# Hydra_OSP.net
KiCad netlist of a schematic drawn in EAGLE
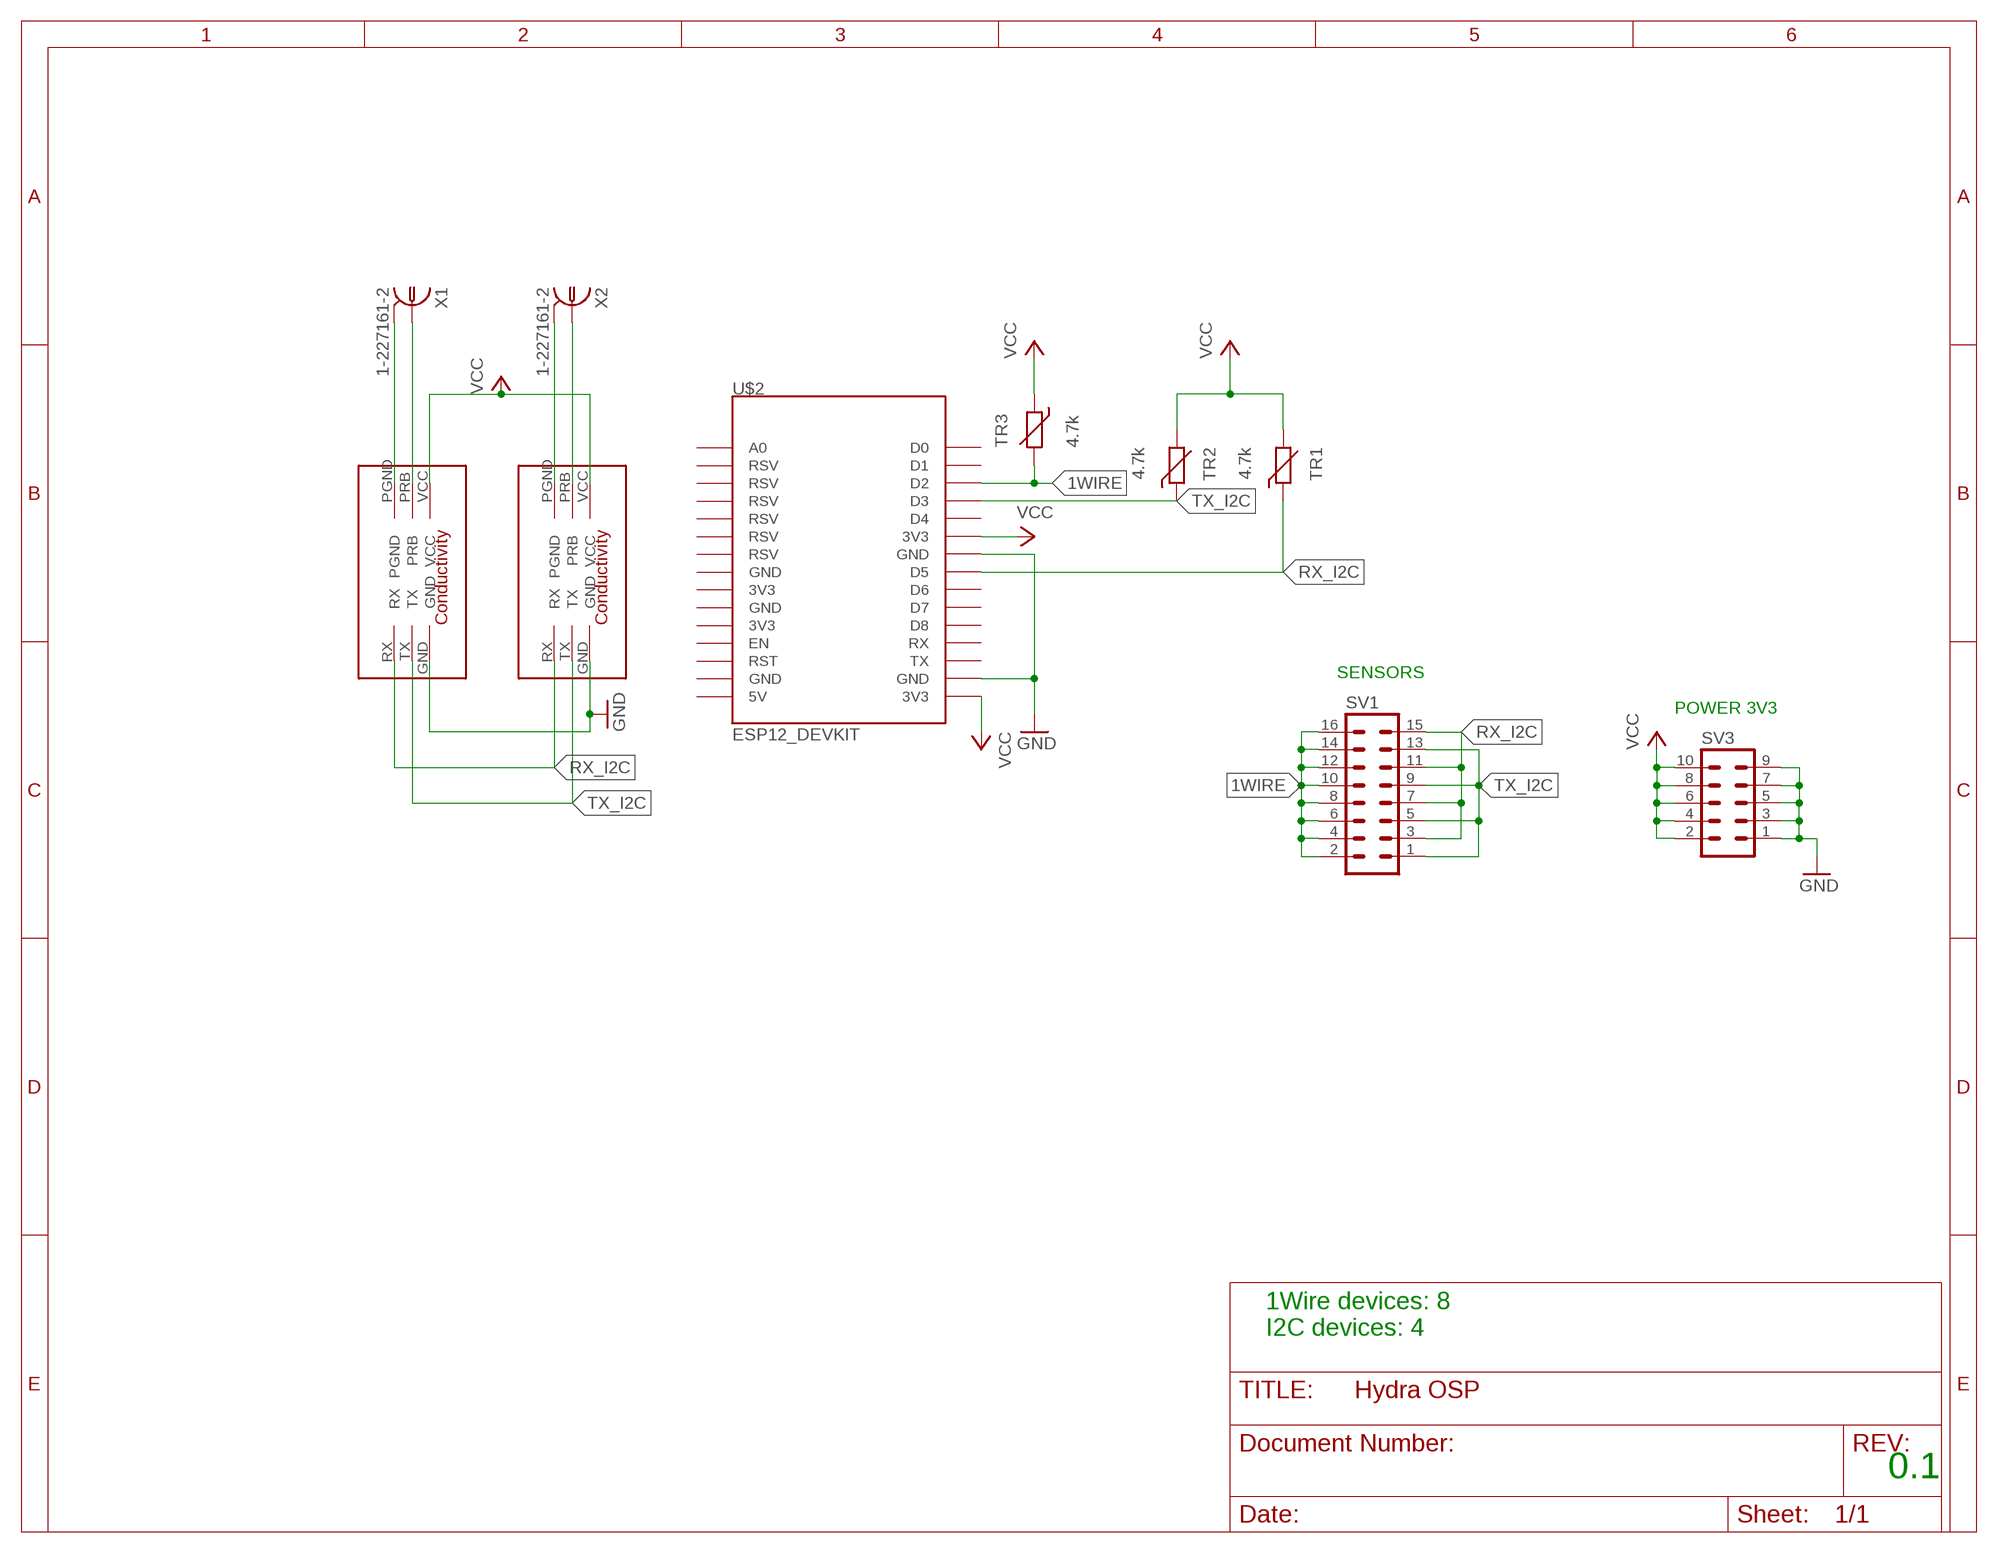
[diagram p0: schematic, sheet 1]

(export (version "E")
  (design (tool "Eeschema 10.0.6"))
  (components
    (comp (ref "SV1")
      (value "MA08-2")
      (footprint "eagle-import:MA08-2")
      (libsource (lib "eagle-import") (part "MA08-2"))
    )
    (comp (ref "SV3")
      (value "MA05-2")
      (footprint "eagle-import:MA05-2")
      (libsource (lib "eagle-import") (part "MA05-2"))
    )
    (comp (ref "TR1")
      (value "4.7k")
      (footprint "eagle-import:R-5")
      (libsource (lib "eagle-import") (part "THERMISTOR_R-5"))
    )
    (comp (ref "TR2")
      (value "4.7k")
      (footprint "eagle-import:R-5")
      (libsource (lib "eagle-import") (part "THERMISTOR_R-5"))
    )
    (comp (ref "TR3")
      (value "4.7k")
      (footprint "eagle-import:R-5")
      (libsource (lib "eagle-import") (part "THERMISTOR_R-5"))
    )
    (comp (ref "U$1")
      (value "ATLSCI_COND")
      (footprint "eagle-import:ATLAS_SCI_COND")
      (libsource (lib "eagle-import") (part "ATLSCI_COND"))
    )
    (comp (ref "U$2")
      (value "ESP12_DEVKIT")
      (footprint "eagle-import:ESP12_DEVKIT")
      (libsource (lib "eagle-import") (part "ESP12_DEVKIT"))
    )
    (comp (ref "U$3")
      (value "ATLSCI_COND")
      (footprint "eagle-import:ATLAS_SCI_COND")
      (libsource (lib "eagle-import") (part "ATLSCI_COND"))
    )
    (comp (ref "X1")
      (value "1-227161-2")
      (footprint "eagle-import:AMP_227161")
      (libsource (lib "eagle-import") (part "?2271611--2"))
    )
    (comp (ref "X2")
      (value "1-227161-2")
      (footprint "eagle-import:AMP_227161")
      (libsource (lib "eagle-import") (part "?2271611--2"))
    )
  )
  (nets
    (net (code "1") (name "1WIRE") (class "Default")
      (node (ref "SV1") (pin "10") (pinfunction "10_10") (pintype "passive"))
      (node (ref "SV1") (pin "12") (pinfunction "12_12") (pintype "passive"))
      (node (ref "SV1") (pin "14") (pinfunction "14_14") (pintype "passive"))
      (node (ref "SV1") (pin "16") (pinfunction "16_16") (pintype "passive"))
      (node (ref "SV1") (pin "2") (pinfunction "2_2") (pintype "passive"))
      (node (ref "SV1") (pin "4") (pinfunction "4_4") (pintype "passive"))
      (node (ref "SV1") (pin "6") (pinfunction "6_6") (pintype "passive"))
      (node (ref "SV1") (pin "8") (pinfunction "8_8") (pintype "passive"))
      (node (ref "TR3") (pin "2") (pinfunction "2_2") (pintype "passive"))
      (node (ref "U$2") (pin "D2") (pinfunction "D2_D2") (pintype "bidirectional"))
    )
    (net (code "2") (name "GND") (class "Default")
      (node (ref "SV3") (pin "1") (pinfunction "1_1") (pintype "passive"))
      (node (ref "SV3") (pin "3") (pinfunction "3_3") (pintype "passive"))
      (node (ref "SV3") (pin "5") (pinfunction "5_5") (pintype "passive"))
      (node (ref "SV3") (pin "7") (pinfunction "7_7") (pintype "passive"))
      (node (ref "SV3") (pin "9") (pinfunction "9_9") (pintype "passive"))
      (node (ref "U$1") (pin "GND") (pinfunction "GND_GND") (pintype "bidirectional"))
      (node (ref "U$2") (pin "GND@2") (pinfunction "GND_GND@2") (pintype "bidirectional"))
      (node (ref "U$2") (pin "GND@3") (pinfunction "GND_GND@3") (pintype "bidirectional"))
      (node (ref "U$3") (pin "GND") (pinfunction "GND_GND") (pintype "bidirectional"))
    )
    (net (code "3") (name "Net-(U$1-PadPGND)") (class "Default")
      (node (ref "U$1") (pin "PGND") (pinfunction "PGND_PGND") (pintype "bidirectional"))
      (node (ref "X1") (pin "2") (pinfunction "2_2") (pintype "passive"))
    )
    (net (code "4") (name "Net-(U$1-PadPRB)") (class "Default")
      (node (ref "U$1") (pin "PRB") (pinfunction "PRB_PRB") (pintype "bidirectional"))
      (node (ref "X1") (pin "1") (pinfunction "1_1") (pintype "passive"))
    )
    (net (code "5") (name "Net-(U$3-PadPGND)") (class "Default")
      (node (ref "U$3") (pin "PGND") (pinfunction "PGND_PGND") (pintype "bidirectional"))
      (node (ref "X2") (pin "2") (pinfunction "2_2") (pintype "passive"))
    )
    (net (code "6") (name "Net-(U$3-PadPRB)") (class "Default")
      (node (ref "U$3") (pin "PRB") (pinfunction "PRB_PRB") (pintype "bidirectional"))
      (node (ref "X2") (pin "1") (pinfunction "1_1") (pintype "passive"))
    )
    (net (code "7") (name "RX_I2C") (class "Default")
      (node (ref "SV1") (pin "11") (pinfunction "11_11") (pintype "passive"))
      (node (ref "SV1") (pin "15") (pinfunction "15_15") (pintype "passive"))
      (node (ref "SV1") (pin "3") (pinfunction "3_3") (pintype "passive"))
      (node (ref "SV1") (pin "7") (pinfunction "7_7") (pintype "passive"))
      (node (ref "TR1") (pin "1") (pinfunction "1_1") (pintype "passive"))
      (node (ref "U$1") (pin "RX") (pinfunction "RX_RX") (pintype "bidirectional"))
      (node (ref "U$2") (pin "D5") (pinfunction "D5_D5") (pintype "bidirectional"))
      (node (ref "U$3") (pin "RX") (pinfunction "RX_RX") (pintype "bidirectional"))
    )
    (net (code "8") (name "TX_I2C") (class "Default")
      (node (ref "SV1") (pin "1") (pinfunction "1_1") (pintype "passive"))
      (node (ref "SV1") (pin "13") (pinfunction "13_13") (pintype "passive"))
      (node (ref "SV1") (pin "5") (pinfunction "5_5") (pintype "passive"))
      (node (ref "SV1") (pin "9") (pinfunction "9_9") (pintype "passive"))
      (node (ref "TR2") (pin "1") (pinfunction "1_1") (pintype "passive"))
      (node (ref "U$1") (pin "TX") (pinfunction "TX_TX") (pintype "bidirectional"))
      (node (ref "U$2") (pin "D3") (pinfunction "D3_D3") (pintype "bidirectional"))
      (node (ref "U$3") (pin "TX") (pinfunction "TX_TX") (pintype "bidirectional"))
    )
    (net (code "9") (name "VCC") (class "Default")
      (node (ref "SV3") (pin "10") (pinfunction "10_10") (pintype "passive"))
      (node (ref "SV3") (pin "2") (pinfunction "2_2") (pintype "passive"))
      (node (ref "SV3") (pin "4") (pinfunction "4_4") (pintype "passive"))
      (node (ref "SV3") (pin "6") (pinfunction "6_6") (pintype "passive"))
      (node (ref "SV3") (pin "8") (pinfunction "8_8") (pintype "passive"))
      (node (ref "TR1") (pin "2") (pinfunction "2_2") (pintype "passive"))
      (node (ref "TR2") (pin "2") (pinfunction "2_2") (pintype "passive"))
      (node (ref "TR3") (pin "1") (pinfunction "1_1") (pintype "passive"))
      (node (ref "U$1") (pin "VCC") (pinfunction "VCC_VCC") (pintype "bidirectional"))
      (node (ref "U$2") (pin "3V3@1") (pinfunction "3V3_3V3@1") (pintype "bidirectional"))
      (node (ref "U$2") (pin "3V3@2") (pinfunction "3V3_3V3@2") (pintype "bidirectional"))
      (node (ref "U$3") (pin "VCC") (pinfunction "VCC_VCC") (pintype "bidirectional"))
    )
    (net (code "10") (name "unconnected-(U$2-3V3-Pad3V3@0)") (class "Default")
      (node (ref "U$2") (pin "3V3@0") (pinfunction "3V3_3V3@0") (pintype "bidirectional"))
    )
    (net (code "11") (name "unconnected-(U$2-3V3-Pad3V3@3)") (class "Default")
      (node (ref "U$2") (pin "3V3@3") (pinfunction "3V3_3V3@3") (pintype "bidirectional"))
    )
    (net (code "12") (name "unconnected-(U$2-GND-PadGND@0)") (class "Default")
      (node (ref "U$2") (pin "GND@0") (pinfunction "GND_GND@0") (pintype "bidirectional"))
    )
    (net (code "13") (name "unconnected-(U$2-GND-PadGND@1)") (class "Default")
      (node (ref "U$2") (pin "GND@1") (pinfunction "GND_GND@1") (pintype "bidirectional"))
    )
    (net (code "14") (name "unconnected-(U$2-GND-PadGND@4)") (class "Default")
      (node (ref "U$2") (pin "GND@4") (pinfunction "GND_GND@4") (pintype "bidirectional"))
    )
    (net (code "15") (name "unconnected-(U$2-Pad5V)") (class "Default")
      (node (ref "U$2") (pin "5V") (pinfunction "5V_5V") (pintype "bidirectional"))
    )
    (net (code "16") (name "unconnected-(U$2-PadA0)") (class "Default")
      (node (ref "U$2") (pin "A0") (pinfunction "A0_A0") (pintype "bidirectional"))
    )
    (net (code "17") (name "unconnected-(U$2-PadD0)") (class "Default")
      (node (ref "U$2") (pin "D0") (pinfunction "D0_D0") (pintype "bidirectional"))
    )
    (net (code "18") (name "unconnected-(U$2-PadD1)") (class "Default")
      (node (ref "U$2") (pin "D1") (pinfunction "D1_D1") (pintype "bidirectional"))
    )
    (net (code "19") (name "unconnected-(U$2-PadD4)") (class "Default")
      (node (ref "U$2") (pin "D4") (pinfunction "D4_D4") (pintype "bidirectional"))
    )
    (net (code "20") (name "unconnected-(U$2-PadD6)") (class "Default")
      (node (ref "U$2") (pin "D6") (pinfunction "D6_D6") (pintype "bidirectional"))
    )
    (net (code "21") (name "unconnected-(U$2-PadD7)") (class "Default")
      (node (ref "U$2") (pin "D7") (pinfunction "D7_D7") (pintype "bidirectional"))
    )
    (net (code "22") (name "unconnected-(U$2-PadD8)") (class "Default")
      (node (ref "U$2") (pin "D8") (pinfunction "D8_D8") (pintype "bidirectional"))
    )
    (net (code "23") (name "unconnected-(U$2-PadEN)") (class "Default")
      (node (ref "U$2") (pin "EN") (pinfunction "EN_EN") (pintype "bidirectional"))
    )
    (net (code "24") (name "unconnected-(U$2-PadRST)") (class "Default")
      (node (ref "U$2") (pin "RST") (pinfunction "RST_RST") (pintype "bidirectional"))
    )
    (net (code "25") (name "unconnected-(U$2-PadRX)") (class "Default")
      (node (ref "U$2") (pin "RX") (pinfunction "RX_RX") (pintype "bidirectional"))
    )
    (net (code "26") (name "unconnected-(U$2-PadTX)") (class "Default")
      (node (ref "U$2") (pin "TX") (pinfunction "TX_TX") (pintype "bidirectional"))
    )
    (net (code "27") (name "unconnected-(U$2-RSV-PadRSV@0)") (class "Default")
      (node (ref "U$2") (pin "RSV@0") (pinfunction "RSV_RSV@0") (pintype "bidirectional"))
    )
    (net (code "28") (name "unconnected-(U$2-RSV-PadRSV@1)") (class "Default")
      (node (ref "U$2") (pin "RSV@1") (pinfunction "RSV_RSV@1") (pintype "bidirectional"))
    )
    (net (code "29") (name "unconnected-(U$2-RSV-PadRSV@2)") (class "Default")
      (node (ref "U$2") (pin "RSV@2") (pinfunction "RSV_RSV@2") (pintype "bidirectional"))
    )
    (net (code "30") (name "unconnected-(U$2-RSV-PadRSV@3)") (class "Default")
      (node (ref "U$2") (pin "RSV@3") (pinfunction "RSV_RSV@3") (pintype "bidirectional"))
    )
    (net (code "31") (name "unconnected-(U$2-RSV-PadRSV@4)") (class "Default")
      (node (ref "U$2") (pin "RSV@4") (pinfunction "RSV_RSV@4") (pintype "bidirectional"))
    )
    (net (code "32") (name "unconnected-(U$2-RSV-PadRSV@5)") (class "Default")
      (node (ref "U$2") (pin "RSV@5") (pinfunction "RSV_RSV@5") (pintype "bidirectional"))
    )
  )
)
